# Group11.net
KiCad netlist of a schematic drawn in EAGLE
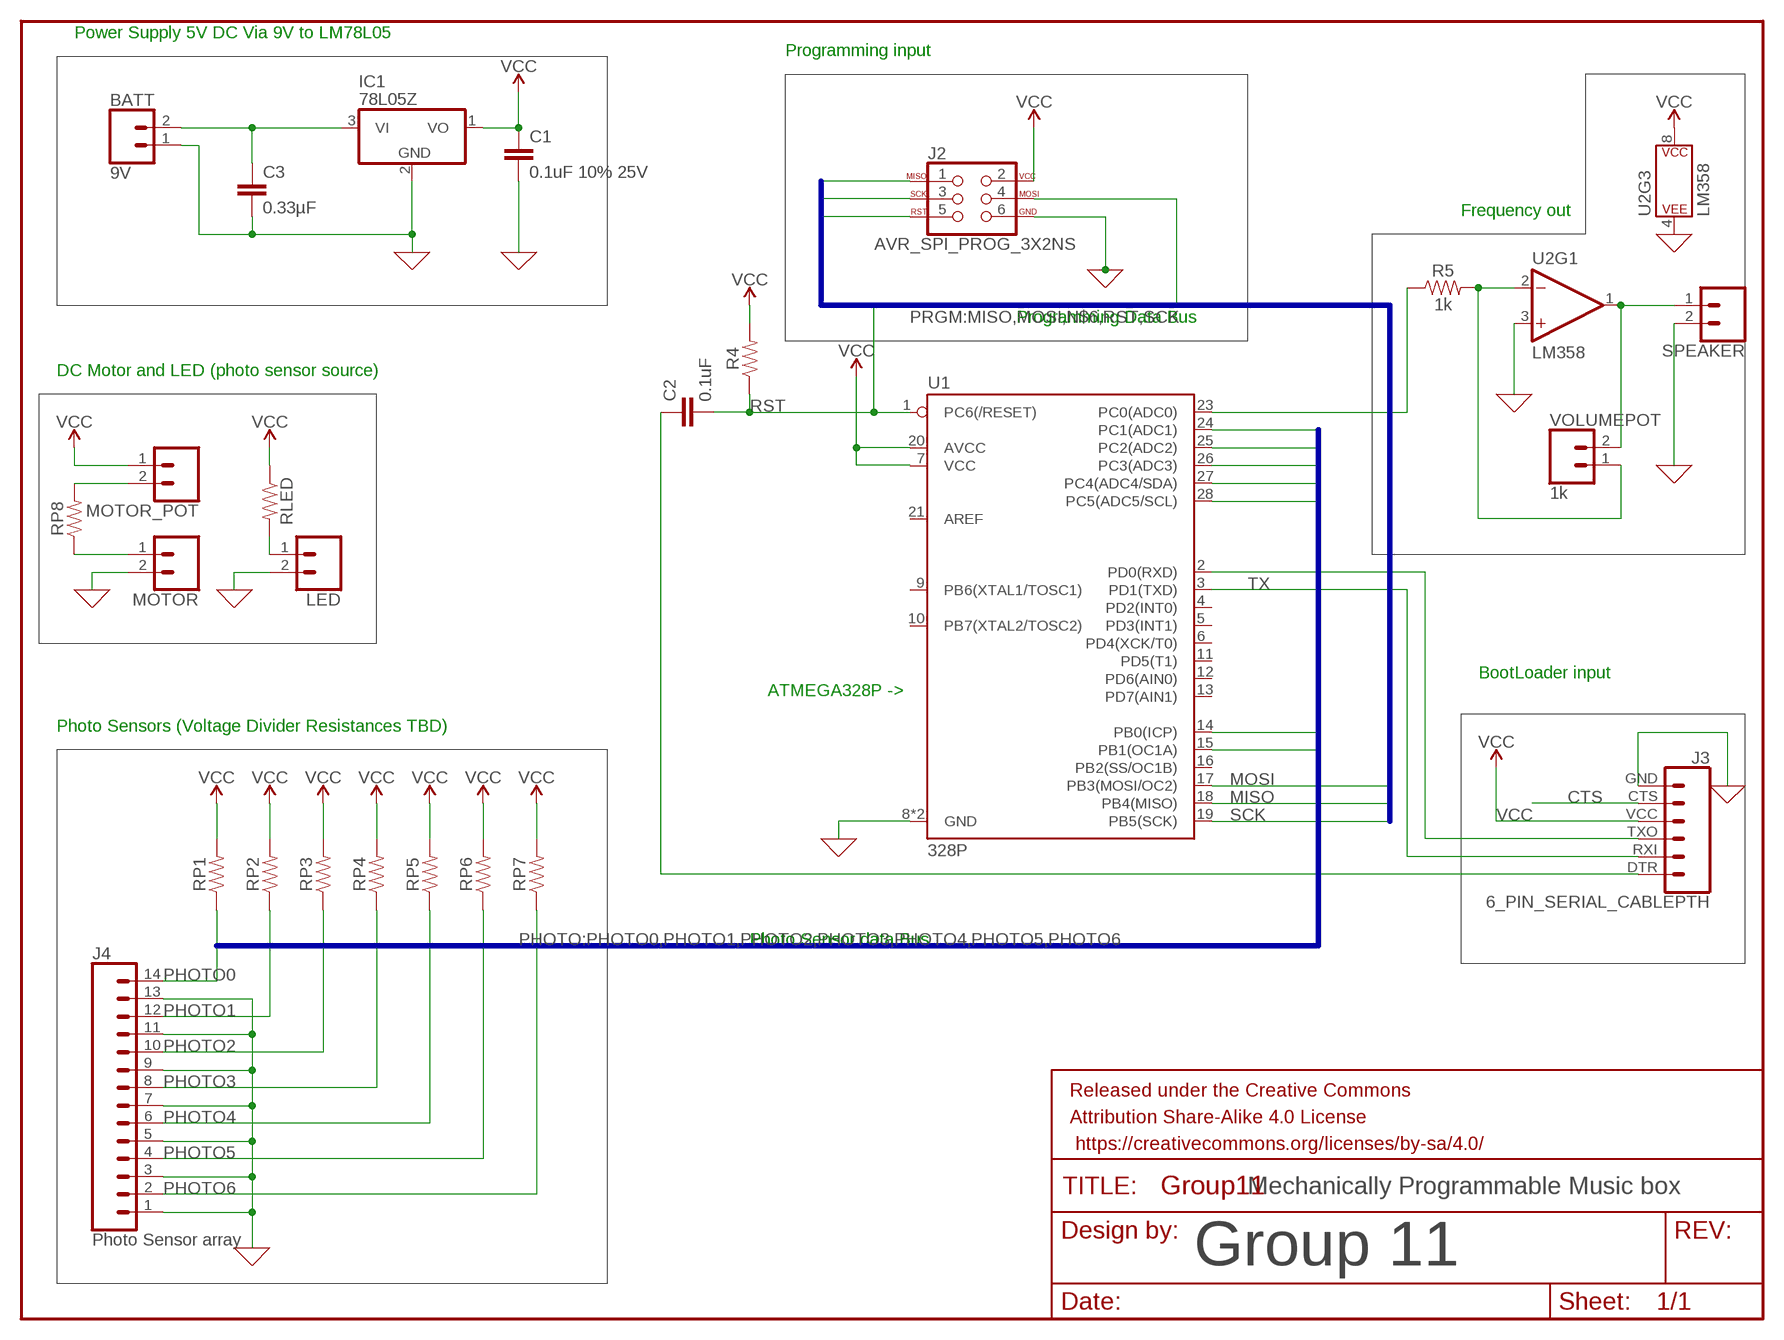
[diagram p0: schematic, sheet 1]

(export (version "E")
  (design (tool "Eeschema 10.0.6"))
  (components
    (comp (ref "BATT")
      (value "9V")
      (footprint "eagle-import:1X02")
      (libsource (lib "eagle-import") (part "CONN_02"))
    )
    (comp (ref "C1")
      (value "0.1uF 10% 25V")
      (footprint "eagle-import:0603")
      (libsource (lib "eagle-import") (part "0.1UF-0603-25V-(+80/-20%)"))
    )
    (comp (ref "C2")
      (value "0.1uF")
      (footprint "eagle-import:0603")
      (libsource (lib "eagle-import") (part "0.1UF-0603-25V-(+80/-20%)"))
    )
    (comp (ref "C3")
      (value "0.33µF")
      (footprint "eagle-import:0805")
      (libsource (lib "eagle-import") (part "0.33UF/330NF-0805-50V-10%"))
    )
    (comp (ref "FRAME1")
      (value "FRAME-LETTER")
      (footprint "eagle-import:CREATIVE_COMMONS")
      (libsource (lib "eagle-import") (part "FRAME-LETTER"))
    )
    (comp (ref "IC1")
      (value "78L05Z")
      (footprint "eagle-import:TO92")
      (libsource (lib "eagle-import") (part "78ZL05"))
    )
    (comp (ref "J2")
      (value "AVR_SPI_PROG_3X2NS")
      (footprint "eagle-import:2X3-NS")
      (libsource (lib "eagle-import") (part "AVR_SPI_PROG_3X2NS"))
    )
    (comp (ref "J3")
      (value "6_PIN_SERIAL_CABLEPTH")
      (footprint "eagle-import:FTDI_BASIC")
      (libsource (lib "eagle-import") (part "6_PIN_SERIAL_CABLEPTH"))
    )
    (comp (ref "J4")
      (value "Photo Sensor array")
      (footprint "eagle-import:1X14")
      (libsource (lib "eagle-import") (part "CONN_14"))
    )
    (comp (ref "LED")
      (value "CONN_02")
      (footprint "eagle-import:1X02")
      (libsource (lib "eagle-import") (part "CONN_02"))
    )
    (comp (ref "MOTOR")
      (value "CONN_02")
      (footprint "eagle-import:1X02")
      (libsource (lib "eagle-import") (part "CONN_02"))
    )
    (comp (ref "MOTOR_POT")
      (value "CONN_02")
      (footprint "eagle-import:1X02")
      (libsource (lib "eagle-import") (part "CONN_02"))
    )
    (comp (ref "R4")
      (value "RESISTOR0805")
      (footprint "eagle-import:0805")
      (libsource (lib "eagle-import") (part "RESISTOR0805"))
    )
    (comp (ref "R5")
      (value "1k")
      (footprint "eagle-import:0603")
      (libsource (lib "eagle-import") (part "1KOHM-0603-1/10W-1%"))
    )
    (comp (ref "RLED")
      (value "RESISTOR0603")
      (footprint "eagle-import:0603")
      (libsource (lib "eagle-import") (part "RESISTOR0603"))
    )
    (comp (ref "RP1")
      (value "RESISTOR0603")
      (footprint "eagle-import:0603")
      (libsource (lib "eagle-import") (part "RESISTOR0603"))
    )
    (comp (ref "RP2")
      (value "RESISTOR0603")
      (footprint "eagle-import:0603")
      (libsource (lib "eagle-import") (part "RESISTOR0603"))
    )
    (comp (ref "RP3")
      (value "RESISTOR0603")
      (footprint "eagle-import:0603")
      (libsource (lib "eagle-import") (part "RESISTOR0603"))
    )
    (comp (ref "RP4")
      (value "RESISTOR0603")
      (footprint "eagle-import:0603")
      (libsource (lib "eagle-import") (part "RESISTOR0603"))
    )
    (comp (ref "RP5")
      (value "RESISTOR0603")
      (footprint "eagle-import:0603")
      (libsource (lib "eagle-import") (part "RESISTOR0603"))
    )
    (comp (ref "RP6")
      (value "RESISTOR0603")
      (footprint "eagle-import:0603")
      (libsource (lib "eagle-import") (part "RESISTOR0603"))
    )
    (comp (ref "RP7")
      (value "RESISTOR0603")
      (footprint "eagle-import:0603")
      (libsource (lib "eagle-import") (part "RESISTOR0603"))
    )
    (comp (ref "RP8")
      (value "RESISTOR0603")
      (footprint "eagle-import:0603")
      (libsource (lib "eagle-import") (part "RESISTOR0603"))
    )
    (comp (ref "SPEAKER")
      (value "CONN_02")
      (footprint "eagle-import:1X02")
      (libsource (lib "eagle-import") (part "CONN_02"))
    )
    (comp (ref "U1")
      (value "328P")
      (footprint "eagle-import:DIP28")
      (libsource (lib "eagle-import") (part "ATMEGA328P_PDIP"))
    )
    (comp (ref "U2")
      (value "LM358")
      (footprint "eagle-import:DIP08")
      (libsource (lib "eagle-import") (part "LM358"))
    )
    (comp (ref "VOLUMEPOT")
      (value "1k")
      (footprint "eagle-import:1X02")
      (libsource (lib "eagle-import") (part "CONN_02"))
    )
  )
  (nets
    (net (code "4") (name "/CTS") (class "Default")
      (node (ref "J3") (pin "CTS") (pinfunction "5_CTS") (pintype "passive"))
    )
    (net (code "5") (name "/MISO") (class "Default")
      (node (ref "J2") (pin "1") (pinfunction "1_1") (pintype "passive"))
      (node (ref "U1") (pin "18") (pinfunction "PB4(MISO)_18") (pintype "bidirectional"))
    )
    (net (code "6") (name "/MOSI") (class "Default")
      (node (ref "J2") (pin "4") (pinfunction "4_4") (pintype "passive"))
      (node (ref "U1") (pin "17") (pinfunction "PB3(MOSI/OC2)_17") (pintype "bidirectional"))
    )
    (net (code "7") (name "/PHOTO0") (class "Default")
      (node (ref "J4") (pin "14") (pinfunction "14_14") (pintype "passive"))
      (node (ref "RP1") (pin "1") (pinfunction "1_1") (pintype "passive"))
      (node (ref "U1") (pin "24") (pinfunction "PC1(ADC1)_24") (pintype "bidirectional"))
    )
    (net (code "8") (name "/PHOTO1") (class "Default")
      (node (ref "J4") (pin "12") (pinfunction "12_12") (pintype "passive"))
      (node (ref "RP2") (pin "1") (pinfunction "1_1") (pintype "passive"))
      (node (ref "U1") (pin "25") (pinfunction "PC2(ADC2)_25") (pintype "bidirectional"))
    )
    (net (code "9") (name "/PHOTO2") (class "Default")
      (node (ref "J4") (pin "10") (pinfunction "10_10") (pintype "passive"))
      (node (ref "RP3") (pin "1") (pinfunction "1_1") (pintype "passive"))
      (node (ref "U1") (pin "26") (pinfunction "PC3(ADC3)_26") (pintype "bidirectional"))
    )
    (net (code "10") (name "/PHOTO3") (class "Default")
      (node (ref "J4") (pin "8") (pinfunction "8_8") (pintype "passive"))
      (node (ref "RP4") (pin "1") (pinfunction "1_1") (pintype "passive"))
      (node (ref "U1") (pin "27") (pinfunction "PC4(ADC4/SDA)_27") (pintype "bidirectional"))
    )
    (net (code "11") (name "/PHOTO4") (class "Default")
      (node (ref "J4") (pin "6") (pinfunction "6_6") (pintype "passive"))
      (node (ref "RP5") (pin "1") (pinfunction "1_1") (pintype "passive"))
      (node (ref "U1") (pin "28") (pinfunction "PC5(ADC5/SCL)_28") (pintype "bidirectional"))
    )
    (net (code "12") (name "/PHOTO5") (class "Default")
      (node (ref "J4") (pin "4") (pinfunction "4_4") (pintype "passive"))
      (node (ref "RP6") (pin "1") (pinfunction "1_1") (pintype "passive"))
      (node (ref "U1") (pin "14") (pinfunction "PB0(ICP)_14") (pintype "bidirectional"))
    )
    (net (code "13") (name "/PHOTO6") (class "Default")
      (node (ref "J4") (pin "2") (pinfunction "2_2") (pintype "passive"))
      (node (ref "RP7") (pin "1") (pinfunction "1_1") (pintype "passive"))
      (node (ref "U1") (pin "15") (pinfunction "PB1(OC1A)_15") (pintype "bidirectional"))
    )
    (net (code "14") (name "/RST") (class "Default")
      (node (ref "C2") (pin "2") (pinfunction "2_2") (pintype "passive"))
      (node (ref "J2") (pin "5") (pinfunction "5_5") (pintype "passive"))
      (node (ref "R4") (pin "1") (pinfunction "1_1") (pintype "passive"))
      (node (ref "U1") (pin "1") (pinfunction "PC6(/RESET)_1") (pintype "bidirectional"))
    )
    (net (code "15") (name "/SCK") (class "Default")
      (node (ref "J2") (pin "3") (pinfunction "3_3") (pintype "passive"))
      (node (ref "U1") (pin "19") (pinfunction "PB5(SCK)_19") (pintype "bidirectional"))
    )
    (net (code "16") (name "/TX") (class "Default")
      (node (ref "J3") (pin "RXI") (pinfunction "2_RXI") (pintype "passive"))
      (node (ref "U1") (pin "3") (pinfunction "PD1(TXD)_3") (pintype "bidirectional"))
    )
    (net (code "19") (name "GND") (class "Default")
      (node (ref "BATT") (pin "1") (pinfunction "1_1") (pintype "passive"))
      (node (ref "C1") (pin "2") (pinfunction "2_2") (pintype "passive"))
      (node (ref "C3") (pin "2") (pinfunction "2_2") (pintype "passive"))
      (node (ref "IC1") (pin "2") (pinfunction "GND_2") (pintype "passive"))
      (node (ref "J2") (pin "6") (pinfunction "6_6") (pintype "passive"))
      (node (ref "J3") (pin "GND") (pinfunction "6_GND") (pintype "passive"))
      (node (ref "J4") (pin "1") (pinfunction "1_1") (pintype "passive"))
      (node (ref "J4") (pin "11") (pinfunction "11_11") (pintype "passive"))
      (node (ref "J4") (pin "13") (pinfunction "13_13") (pintype "passive"))
      (node (ref "J4") (pin "3") (pinfunction "3_3") (pintype "passive"))
      (node (ref "J4") (pin "5") (pinfunction "5_5") (pintype "passive"))
      (node (ref "J4") (pin "7") (pinfunction "7_7") (pintype "passive"))
      (node (ref "J4") (pin "9") (pinfunction "9_9") (pintype "passive"))
      (node (ref "LED") (pin "2") (pinfunction "2_2") (pintype "passive"))
      (node (ref "MOTOR") (pin "2") (pinfunction "2_2") (pintype "passive"))
      (node (ref "SPEAKER") (pin "2") (pinfunction "2_2") (pintype "passive"))
      (node (ref "U1") (pin "22") (pinfunction "GND_22") (pintype "bidirectional"))
      (node (ref "U1") (pin "8") (pinfunction "GND_8") (pintype "bidirectional"))
      (node (ref "U2") (pin "3") (pinfunction "+IN_3") (pintype "input"))
      (node (ref "U2") (pin "4") (pinfunction "P$V-_4") (pintype "bidirectional"))
    )
    (net (code "20") (name "Net-(IC1-VI)") (class "Default")
      (node (ref "BATT") (pin "2") (pinfunction "2_2") (pintype "passive"))
      (node (ref "C3") (pin "1") (pinfunction "1_1") (pintype "passive"))
      (node (ref "IC1") (pin "3") (pinfunction "VI_3") (pintype "input"))
    )
    (net (code "21") (name "Net-(J3-1)") (class "Default")
      (node (ref "C2") (pin "1") (pinfunction "1_1") (pintype "passive"))
      (node (ref "J3") (pin "DTR") (pinfunction "1_DTR") (pintype "passive"))
    )
    (net (code "22") (name "Net-(J3-3)") (class "Default")
      (node (ref "J3") (pin "TXO") (pinfunction "3_TXO") (pintype "passive"))
      (node (ref "U1") (pin "2") (pinfunction "PD0(RXD)_2") (pintype "bidirectional"))
    )
    (net (code "23") (name "Net-(LED-Pad1)") (class "Default")
      (node (ref "LED") (pin "1") (pinfunction "1_1") (pintype "passive"))
      (node (ref "RLED") (pin "2") (pinfunction "2_2") (pintype "passive"))
    )
    (net (code "24") (name "Net-(MOTOR-Pad1)") (class "Default")
      (node (ref "MOTOR") (pin "1") (pinfunction "1_1") (pintype "passive"))
      (node (ref "RP8") (pin "1") (pinfunction "1_1") (pintype "passive"))
    )
    (net (code "25") (name "Net-(MOTOR_POT-Pad2)") (class "Default")
      (node (ref "MOTOR_POT") (pin "2") (pinfunction "2_2") (pintype "passive"))
      (node (ref "RP8") (pin "2") (pinfunction "2_2") (pintype "passive"))
    )
    (net (code "26") (name "Net-(U1-PC0(ADC0))") (class "Default")
      (node (ref "R5") (pin "1") (pinfunction "1_1") (pintype "passive"))
      (node (ref "U1") (pin "23") (pinfunction "PC0(ADC0)_23") (pintype "bidirectional"))
    )
    (net (code "27") (name "Net-(U2A--IN)") (class "Default")
      (node (ref "R5") (pin "2") (pinfunction "2_2") (pintype "passive"))
      (node (ref "U2") (pin "2") (pinfunction "-IN_2") (pintype "input"))
      (node (ref "VOLUMEPOT") (pin "1") (pinfunction "1_1") (pintype "passive"))
    )
    (net (code "28") (name "Net-(U2A-OUT)") (class "Default")
      (node (ref "SPEAKER") (pin "1") (pinfunction "1_1") (pintype "passive"))
      (node (ref "U2") (pin "1") (pinfunction "OUT_1") (pintype "output"))
      (node (ref "VOLUMEPOT") (pin "2") (pinfunction "2_2") (pintype "passive"))
    )
    (net (code "29") (name "VCC") (class "Default")
      (node (ref "C1") (pin "1") (pinfunction "1_1") (pintype "passive"))
      (node (ref "IC1") (pin "1") (pinfunction "VO_1") (pintype "passive"))
      (node (ref "J2") (pin "2") (pinfunction "2_2") (pintype "passive"))
      (node (ref "J3") (pin "VCC") (pinfunction "4_VCC") (pintype "passive"))
      (node (ref "MOTOR_POT") (pin "1") (pinfunction "1_1") (pintype "passive"))
      (node (ref "R4") (pin "2") (pinfunction "2_2") (pintype "passive"))
      (node (ref "RLED") (pin "1") (pinfunction "1_1") (pintype "passive"))
      (node (ref "RP1") (pin "2") (pinfunction "2_2") (pintype "passive"))
      (node (ref "RP2") (pin "2") (pinfunction "2_2") (pintype "passive"))
      (node (ref "RP3") (pin "2") (pinfunction "2_2") (pintype "passive"))
      (node (ref "RP4") (pin "2") (pinfunction "2_2") (pintype "passive"))
      (node (ref "RP5") (pin "2") (pinfunction "2_2") (pintype "passive"))
      (node (ref "RP6") (pin "2") (pinfunction "2_2") (pintype "passive"))
      (node (ref "RP7") (pin "2") (pinfunction "2_2") (pintype "passive"))
      (node (ref "U1") (pin "20") (pinfunction "AVCC_20") (pintype "bidirectional"))
      (node (ref "U1") (pin "7") (pinfunction "VCC_7") (pintype "bidirectional"))
      (node (ref "U2") (pin "8") (pinfunction "P$V+_8") (pintype "bidirectional"))
    )
    (net (code "30") (name "unconnected-(U1-AREF-Pad21)") (class "Default")
      (node (ref "U1") (pin "21") (pinfunction "AREF_21") (pintype "bidirectional"))
    )
    (net (code "31") (name "unconnected-(U1-PB2(SS{slash}OC1B)-Pad16)") (class "Default")
      (node (ref "U1") (pin "16") (pinfunction "PB2(SS/OC1B)_16") (pintype "bidirectional"))
    )
    (net (code "32") (name "unconnected-(U1-PB6(XTAL1{slash}TOSC1)-Pad9)") (class "Default")
      (node (ref "U1") (pin "9") (pinfunction "PB6(XTAL1/TOSC1)_9") (pintype "bidirectional"))
    )
    (net (code "33") (name "unconnected-(U1-PB7(XTAL2{slash}TOSC2)-Pad10)") (class "Default")
      (node (ref "U1") (pin "10") (pinfunction "PB7(XTAL2/TOSC2)_10") (pintype "bidirectional"))
    )
    (net (code "34") (name "unconnected-(U1-PD2(INT0)-Pad4)") (class "Default")
      (node (ref "U1") (pin "4") (pinfunction "PD2(INT0)_4") (pintype "bidirectional"))
    )
    (net (code "35") (name "unconnected-(U1-PD3(INT1)-Pad5)") (class "Default")
      (node (ref "U1") (pin "5") (pinfunction "PD3(INT1)_5") (pintype "bidirectional"))
    )
    (net (code "36") (name "unconnected-(U1-PD4(XCK{slash}T0)-Pad6)") (class "Default")
      (node (ref "U1") (pin "6") (pinfunction "PD4(XCK/T0)_6") (pintype "bidirectional"))
    )
    (net (code "37") (name "unconnected-(U1-PD5(T1)-Pad11)") (class "Default")
      (node (ref "U1") (pin "11") (pinfunction "PD5(T1)_11") (pintype "bidirectional"))
    )
    (net (code "38") (name "unconnected-(U1-PD6(AIN0)-Pad12)") (class "Default")
      (node (ref "U1") (pin "12") (pinfunction "PD6(AIN0)_12") (pintype "bidirectional"))
    )
    (net (code "39") (name "unconnected-(U1-PD7(AIN1)-Pad13)") (class "Default")
      (node (ref "U1") (pin "13") (pinfunction "PD7(AIN1)_13") (pintype "bidirectional"))
    )
  )
)
